# Comparator.net
KiCad netlist of a schematic drawn in Altium Designer
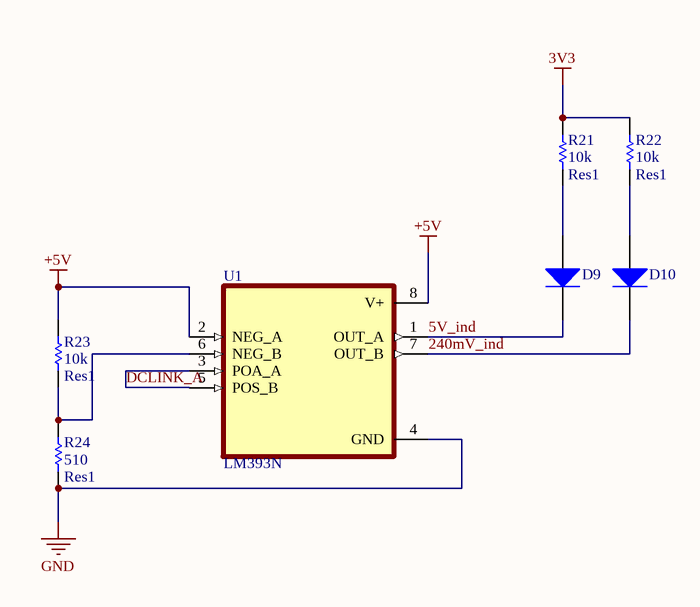
[diagram p0: Comparator.SchDoc]

(export (version "E")
  (design (tool "Eeschema 10.0.6"))
  (components
    (comp (ref "D9")
      (value "Diode 1N4001")
      (footprint "DO-41")
      (description "1 Amp General Purpose Rectifier")
      (fields (field (name "PUBLISHER") "Altium Limited"))
      (libsource (lib "Miscellaneous Devices") (part "Diode 1N4001"))
    )
    (comp (ref "D10")
      (value "Diode 1N4001")
      (footprint "DO-41")
      (description "1 Amp General Purpose Rectifier")
      (fields (field (name "PUBLISHER") "Altium Limited"))
      (libsource (lib "Miscellaneous Devices") (part "Diode 1N4001"))
    )
    (comp (ref "R21")
      (value "Res1")
      (footprint "AXIAL-0.4")
      (description "Resistor")
      (fields (field (name "ALTIUM_VALUE") "10k") (field (name "PUBLISHER") "Altium Limited"))
      (libsource (lib "Miscellaneous Devices") (part "Res1"))
    )
    (comp (ref "R22")
      (value "Res1")
      (footprint "AXIAL-0.4")
      (description "Resistor")
      (fields (field (name "ALTIUM_VALUE") "10k") (field (name "PUBLISHER") "Altium Limited"))
      (libsource (lib "Miscellaneous Devices") (part "Res1"))
    )
    (comp (ref "R23")
      (value "Res1")
      (footprint "AXIAL-0.4")
      (description "Resistor")
      (fields (field (name "ALTIUM_VALUE") "10k") (field (name "PUBLISHER") "Altium Limited"))
      (libsource (lib "Miscellaneous Devices") (part "Res1"))
    )
    (comp (ref "R24")
      (value "Res1")
      (footprint "AXIAL-0.4")
      (description "Resistor")
      (fields (field (name "ALTIUM_VALUE") "510") (field (name "PUBLISHER") "Altium Limited"))
      (libsource (lib "Miscellaneous Devices") (part "Res1"))
    )
    (comp (ref "U1")
      (value "LM393N")
      (footprint "DIP794W45P254L959H508Q8")
      (description "Low Power Low Offset Voltage Dual Comparator 8-PDIP 0 to 70")
      (fields
        (field (name "MF") "Texas Instruments")
        (field (name "DIGI-KEY_PART_NUMBER") "LM393NNS/NOPB-ND")
      )
      (libsource (lib "LM393N") (part "LM393N"))
    )
  )
  (nets
    (net (code "1") (name "+5V") (class "Default")
      (node (ref "R23") (pin "2") (pinfunction "2_2") (pintype "passive"))
      (node (ref "U1") (pin "2") (pinfunction "NEG_A_2") (pintype "input"))
      (node (ref "U1") (pin "8") (pinfunction "V+_8") (pintype "power_in"))
    )
    (net (code "2") (name "/5V_ind") (class "Default")
      (node (ref "D9") (pin "2") (pinfunction "K_2") (pintype "passive"))
      (node (ref "U1") (pin "1") (pinfunction "OUT_A_1") (pintype "output"))
    )
    (net (code "3") (name "/240mV_ind") (class "Default")
      (node (ref "D10") (pin "2") (pinfunction "K_2") (pintype "passive"))
      (node (ref "U1") (pin "7") (pinfunction "OUT_B_7") (pintype "output"))
    )
    (net (code "4") (name "/DCLINK_A") (class "Default")
      (node (ref "U1") (pin "3") (pinfunction "POA_A_3") (pintype "input"))
      (node (ref "U1") (pin "5") (pinfunction "POS_B_5") (pintype "input"))
    )
    (net (code "5") (name "3V3") (class "Default")
      (node (ref "R21") (pin "2") (pinfunction "2_2") (pintype "passive"))
      (node (ref "R22") (pin "2") (pinfunction "2_2") (pintype "passive"))
    )
    (net (code "6") (name "GND") (class "Default")
      (node (ref "R24") (pin "1") (pinfunction "1_1") (pintype "passive"))
      (node (ref "U1") (pin "4") (pinfunction "GND_4") (pintype "power_in"))
    )
    (net (code "7") (name "Net-(D9-A)") (class "Default")
      (node (ref "D9") (pin "1") (pinfunction "A_1") (pintype "passive"))
      (node (ref "R21") (pin "1") (pinfunction "1_1") (pintype "passive"))
    )
    (net (code "8") (name "Net-(D10-A)") (class "Default")
      (node (ref "D10") (pin "1") (pinfunction "A_1") (pintype "passive"))
      (node (ref "R22") (pin "1") (pinfunction "1_1") (pintype "passive"))
    )
    (net (code "9") (name "Net-(U1-NEG_B)") (class "Default")
      (node (ref "R23") (pin "1") (pinfunction "1_1") (pintype "passive"))
      (node (ref "R24") (pin "2") (pinfunction "2_2") (pintype "passive"))
      (node (ref "U1") (pin "6") (pinfunction "NEG_B_6") (pintype "input"))
    )
  )
)
